# SC182029-V3R0-Servo.net
KiCad netlist of a schematic drawn in EAGLE
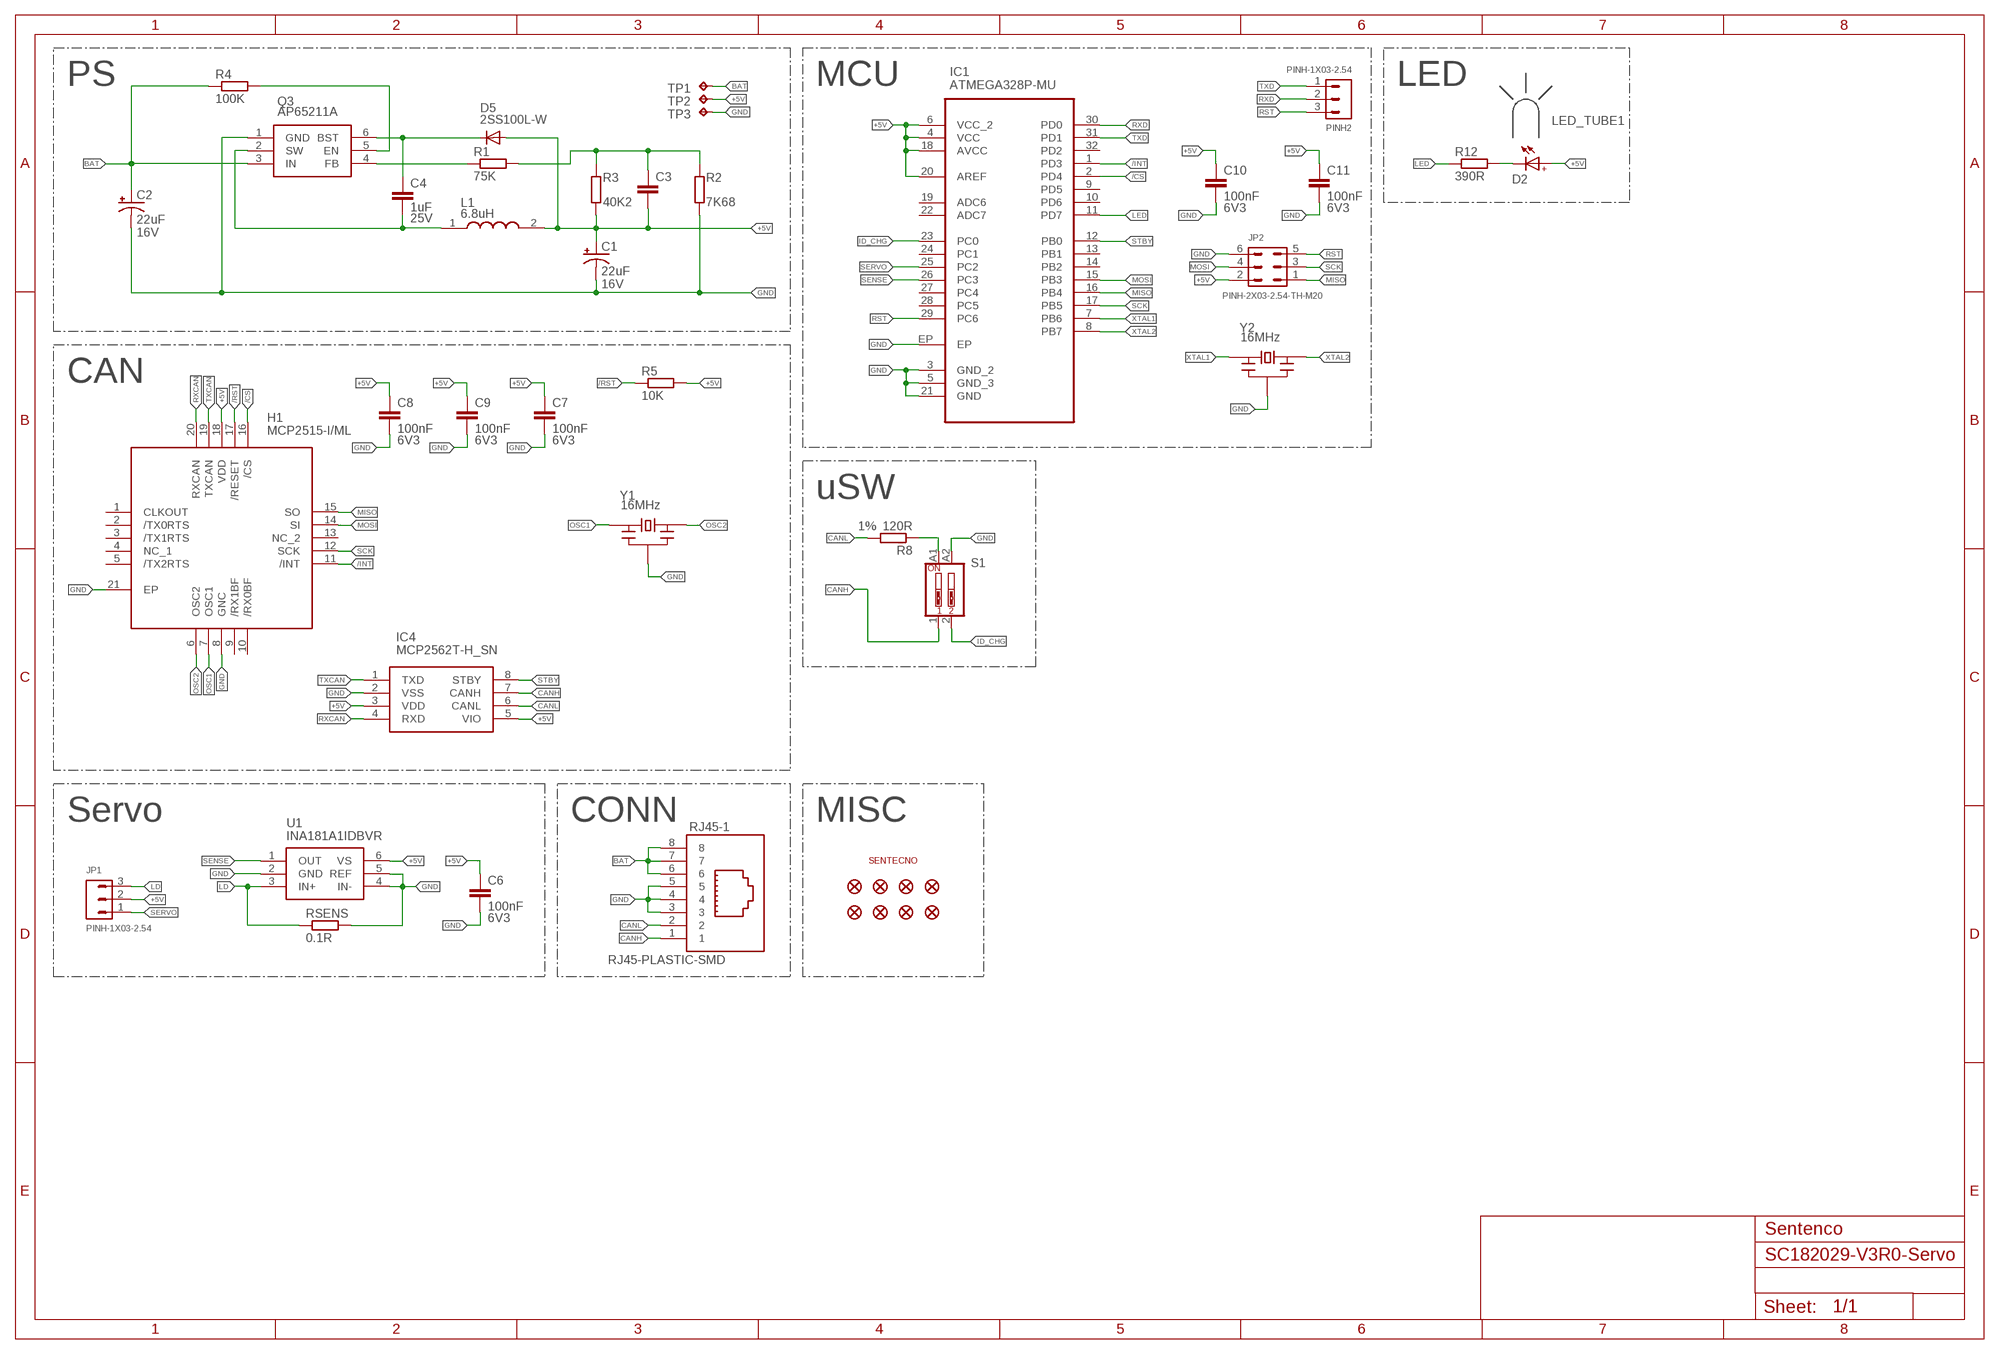
[diagram p0: schematic, sheet 1]

(export (version "E")
  (design (tool "Eeschema 10.0.6"))
  (components
    (comp (ref "C1")
      (value "22uF")
      (footprint "eagle-import:B")
      (fields
        (field (name "MAN1") "Illinois Capacitor / CDE")
        (field (name "MAN1PN") "226SML016MD4")
        (field (name "NOTES") "H5.5mm")
        (field (name "SENTPN") "CESMD-PB-226-16V")
        (field (name "VALUE2") "16V")
      )
      (libsource (lib "eagle-import") (part "COND_PANASONIC_EEE-B"))
    )
    (comp (ref "C2")
      (value "22uF")
      (footprint "eagle-import:B")
      (fields
        (field (name "MAN1") "Illinois Capacitor / CDE")
        (field (name "MAN1PN") "226SML016MD4")
        (field (name "NOTES") "H5.5mm")
        (field (name "SENTPN") "CESMD-PB-226-16V")
        (field (name "VALUE2") "16V")
      )
      (libsource (lib "eagle-import") (part "COND_PANASONIC_EEE-B"))
    )
    (comp (ref "C3")
      (value "COND_CERAMICO_SMD0603R")
      (footprint "eagle-import:C0603R")
      (fields (field (name "BLOCK") "NM"))
      (libsource (lib "eagle-import") (part "COND_CERAMICO_SMD0603R"))
    )
    (comp (ref "C4")
      (value "1uF")
      (footprint "eagle-import:C0603R")
      (fields
        (field (name "BLOCK") "0")
        (field (name "LAYER") "Top")
        (field (name "MAN1") "Taiyo Yuden")
        (field (name "MAN1PN") "TMK107B7105KA-T")
        (field (name "SENTPN") "CCSMD-0603-105-25V")
        (field (name "VALUE2") "25V")
      )
      (libsource (lib "eagle-import") (part "COND_CERAMICO_SMD0603R"))
    )
    (comp (ref "C6")
      (value "100nF")
      (footprint "eagle-import:C0603R")
      (fields
        (field (name "MAN1") "AVX")
        (field (name "MAN1PN") "0603YC104KAT2A")
        (field (name "SENTPN") "CCSMD-0603-104-6V3")
        (field (name "VALUE2") "6V3")
      )
      (libsource (lib "eagle-import") (part "COND_CERAMICO_SMD0603R"))
    )
    (comp (ref "C7")
      (value "100nF")
      (footprint "eagle-import:C0603R")
      (fields
        (field (name "MAN1") "AVX")
        (field (name "MAN1PN") "0603YC104KAT2A")
        (field (name "SENTPN") "CCSMD-0603-104-6V3")
        (field (name "VALUE2") "6V3")
      )
      (libsource (lib "eagle-import") (part "COND_CERAMICO_SMD0603R"))
    )
    (comp (ref "C8")
      (value "100nF")
      (footprint "eagle-import:C0603R")
      (fields
        (field (name "MAN1") "AVX")
        (field (name "MAN1PN") "0603YC104KAT2A")
        (field (name "SENTPN") "CCSMD-0603-104-6V3")
        (field (name "VALUE2") "6V3")
      )
      (libsource (lib "eagle-import") (part "COND_CERAMICO_SMD0603R"))
    )
    (comp (ref "C9")
      (value "100nF")
      (footprint "eagle-import:C0603R")
      (fields
        (field (name "MAN1") "AVX")
        (field (name "MAN1PN") "0603YC104KAT2A")
        (field (name "SENTPN") "CCSMD-0603-104-6V3")
        (field (name "VALUE2") "6V3")
      )
      (libsource (lib "eagle-import") (part "COND_CERAMICO_SMD0603R"))
    )
    (comp (ref "C10")
      (value "100nF")
      (footprint "eagle-import:C0603R")
      (fields
        (field (name "MAN1") "AVX")
        (field (name "MAN1PN") "0603YC104KAT2A")
        (field (name "SENTPN") "CCSMD-0603-104-6V3")
        (field (name "VALUE2") "6V3")
      )
      (libsource (lib "eagle-import") (part "COND_CERAMICO_SMD0603R"))
    )
    (comp (ref "C11")
      (value "100nF")
      (footprint "eagle-import:C0603R")
      (fields
        (field (name "MAN1") "AVX")
        (field (name "MAN1PN") "0603YC104KAT2A")
        (field (name "SENTPN") "CCSMD-0603-104-6V3")
        (field (name "VALUE2") "6V3")
      )
      (libsource (lib "eagle-import") (part "COND_CERAMICO_SMD0603R"))
    )
    (comp (ref "D2")
      (value "WL-SMCW-150060BS75000")
      (footprint "eagle-import:WL-SMCW_0603")
      (fields
        (field (name "MAN1") "Inolux")
        (field (name "MAN1PN") "IN-S63AT5G")
        (field (name "SENTPN") "LEDSMD-0603-GREEN")
      )
      (libsource (lib "eagle-import") (part "WL-SMCW-150060BS75000"))
    )
    (comp (ref "D5")
      (value "2SS100L-W")
      (footprint "eagle-import:SOD-123FL-CUSTOM")
      (fields
        (field (name "BLOCK") "NM")
        (field (name "LAYER") "Top")
        (field (name "MAN1") "Rectron")
        (field (name "MAN1PN") "2SS100L-W")
        (field (name "SENTPN") "2SS100L-W")
      )
      (libsource (lib "eagle-import") (part "DIODE"))
    )
    (comp (ref "FID1")
      (value "FIDUCIALUFIDUCIAL")
      (footprint "eagle-import:MICRO-FIDUCIAL")
      (libsource (lib "eagle-import") (part "FIDUCIALUFIDUCIAL"))
    )
    (comp (ref "FID2")
      (value "FIDUCIALUFIDUCIAL")
      (footprint "eagle-import:MICRO-FIDUCIAL")
      (libsource (lib "eagle-import") (part "FIDUCIALUFIDUCIAL"))
    )
    (comp (ref "FID3")
      (value "FIDUCIALUFIDUCIAL")
      (footprint "eagle-import:MICRO-FIDUCIAL")
      (libsource (lib "eagle-import") (part "FIDUCIALUFIDUCIAL"))
    )
    (comp (ref "FID4")
      (value "FIDUCIALUFIDUCIAL")
      (footprint "eagle-import:MICRO-FIDUCIAL")
      (libsource (lib "eagle-import") (part "FIDUCIALUFIDUCIAL"))
    )
    (comp (ref "FID5")
      (value "FIDUCIALUFIDUCIAL")
      (footprint "eagle-import:MICRO-FIDUCIAL")
      (libsource (lib "eagle-import") (part "FIDUCIALUFIDUCIAL"))
    )
    (comp (ref "FID6")
      (value "FIDUCIALUFIDUCIAL")
      (footprint "eagle-import:MICRO-FIDUCIAL")
      (libsource (lib "eagle-import") (part "FIDUCIALUFIDUCIAL"))
    )
    (comp (ref "FID7")
      (value "FIDUCIALUFIDUCIAL")
      (footprint "eagle-import:MICRO-FIDUCIAL")
      (libsource (lib "eagle-import") (part "FIDUCIALUFIDUCIAL"))
    )
    (comp (ref "FID8")
      (value "FIDUCIALUFIDUCIAL")
      (footprint "eagle-import:MICRO-FIDUCIAL")
      (libsource (lib "eagle-import") (part "FIDUCIALUFIDUCIAL"))
    )
    (comp (ref "H1")
      (value "MCP2515-I/ML")
      (footprint "eagle-import:QFN50P400X400X90-21N")
      (libsource (lib "eagle-import") (part "MCP2515-I/ML"))
    )
    (comp (ref "IC1")
      (value "ATMEGA328P-MU")
      (footprint "eagle-import:QFN50P500X500X100-33N")
      (libsource (lib "eagle-import") (part "ATMEGA328P-MU"))
    )
    (comp (ref "IC4")
      (value "MCP2562T-H_SN")
      (footprint "eagle-import:SOIC127P600X175-8N")
      (libsource (lib "eagle-import") (part "MCP2562T-H_SN"))
    )
    (comp (ref "JP1")
      (value "PINH-1X03-2.54")
      (footprint "eagle-import:PINH-1X03-2.54-1")
      (fields (field (name "MAN1") "Harwin") (field (name "MAN1PN") "M20-9990346"))
      (libsource (lib "eagle-import") (part "PINH-1X03-2.54"))
    )
    (comp (ref "JP2")
      (value "PINH-2X03-2.54-TH-M20")
      (footprint "eagle-import:HDRV6W64P254_2X3_762X508X868P")
      (libsource (lib "eagle-import") (part "PINH-2X03-2.54-TH-M20"))
    )
    (comp (ref "L1")
      (value "6.8uH")
      (footprint "eagle-import:NR5040")
      (libsource (lib "eagle-import") (part "NR5040"))
    )
    (comp (ref "LED_TUBE1")
      (value "LED_TUBEH1")
      (footprint "eagle-import:LED_TUBE_2")
      (libsource (lib "eagle-import") (part "LED_TUBEH1"))
    )
    (comp (ref "LOGO1")
      (value "LOGO_SENTECNOLOGO_6X4MM")
      (footprint "eagle-import:LOGO_6X4MM")
      (libsource (lib "eagle-import") (part "LOGO_SENTECNOLOGO_6X4MM"))
    )
    (comp (ref "PINH2")
      (value "PINH-1X03-2.54")
      (footprint "eagle-import:PINH-1X03-2.54-1")
      (fields (field (name "BLOCK") "NM"))
      (libsource (lib "eagle-import") (part "PINH-1X03-2.54"))
    )
    (comp (ref "Q3")
      (value "AP65211A")
      (footprint "eagle-import:SOT95P280X90-6N")
      (fields
        (field (name "BLOCK") "0")
        (field (name "LAYER") "Top")
        (field (name "MAN1PN") "AP65211A")
        (field (name "SENTPN") "AP65211A")
      )
      (libsource (lib "eagle-import") (part "AP65211A"))
    )
    (comp (ref "R1")
      (value "75K")
      (footprint "eagle-import:R0603R")
      (fields
        (field (name "BLOCK") "0")
        (field (name "LAYER") "Top")
        (field (name "MAN1") "Yageo")
        (field (name "MAN1PN") "RC0603JR-0775KL")
        (field (name "SENTPN") "RSMD-0603-75K")
      )
      (libsource (lib "eagle-import") (part "RES_CERAMICA_SMD0603R"))
    )
    (comp (ref "R2")
      (value "7K68")
      (footprint "eagle-import:R0603R")
      (fields
        (field (name "BLOCK") "0")
        (field (name "LAYER") "Top")
        (field (name "MAN1") "Bourns")
        (field (name "MAN1PN") "CR0603-FX-7681ELF")
        (field (name "MAN2") "RC0603FR-077K68L")
        (field (name "MAN2PN") "Yageo")
        (field (name "SENTPN") "RSMD-0603-7K68")
      )
      (libsource (lib "eagle-import") (part "RES_CERAMICA_SMD0603R"))
    )
    (comp (ref "R3")
      (value "40K2")
      (footprint "eagle-import:R0603R")
      (fields
        (field (name "BLOCK") "0")
        (field (name "LAYER") "Top")
        (field (name "MAN1") "Yageo")
        (field (name "MAN1PN") "RC0603FR-0740K2L")
        (field (name "SENTPN") "RSMD-0603-40K2")
      )
      (libsource (lib "eagle-import") (part "RES_CERAMICA_SMD0603R"))
    )
    (comp (ref "R4")
      (value "100K")
      (footprint "eagle-import:R0603R")
      (fields
        (field (name "BLOCK") "0")
        (field (name "LAYER") "Top")
        (field (name "MAN1") "Bourns")
        (field (name "MAN1PN") "CR0603-JW-104GLF")
        (field (name "SENTPN") "RSMD-0603-100K")
      )
      (libsource (lib "eagle-import") (part "RES_CERAMICA_SMD0603R"))
    )
    (comp (ref "R5")
      (value "10K")
      (footprint "eagle-import:R0603R")
      (fields
        (field (name "MAN1") "Bourns")
        (field (name "MAN1PN") "CR0603-JW-103ELF")
        (field (name "SENTPN") "RSMD-0603-10K")
      )
      (libsource (lib "eagle-import") (part "RES_CERAMICA_SMD0603R"))
    )
    (comp (ref "R8")
      (value "120R")
      (footprint "eagle-import:R0603R")
      (fields
        (field (name "MAN1") "Yageo")
        (field (name "MAN1PN") "RC0603FR-07120RL")
        (field (name "SENTPN") "RSMD-0603R-120R-10")
        (field (name "VALUE2") "1%")
      )
      (libsource (lib "eagle-import") (part "RES_CERAMICA_SMD0603R"))
    )
    (comp (ref "R12")
      (value "390R")
      (footprint "eagle-import:R0603R")
      (fields
        (field (name "MAN1") "Yageo")
        (field (name "MAN1PN") "RC0603FR-07390RL")
        (field (name "SENTPN") "RSMD-0603-390R")
      )
      (libsource (lib "eagle-import") (part "RES_CERAMICA_SMD0603R"))
    )
    (comp (ref "RJ45-1")
      (value "RJ45-PLASTIC-SMD")
      (footprint "eagle-import:73304111LF")
      (libsource (lib "eagle-import") (part "RJ45-PLASTIC-SMD"))
    )
    (comp (ref "RSENS")
      (value "0.1R")
      (footprint "eagle-import:R0603R")
      (fields
        (field (name "MAN1") "Yageo")
        (field (name "MAN1PN") "RL0603JR-070R1L")
        (field (name "SENTPN") "RSMD-0603-0R1")
      )
      (libsource (lib "eagle-import") (part "RES_CERAMICA_SMD0603R"))
    )
    (comp (ref "S1")
      (value "DIP-SW-2")
      (footprint "eagle-import:SMD-DIP-SWITCH-2P")
      (fields (field (name "SENTPN") "SWSMD-1x02"))
      (libsource (lib "eagle-import") (part "DIP-SW-2"))
    )
    (comp (ref "TP1")
      (value "TPTP08R")
      (footprint "eagle-import:TP0.8MMR")
      (libsource (lib "eagle-import") (part "TPTP08R"))
    )
    (comp (ref "TP2")
      (value "TPTP08R")
      (footprint "eagle-import:TP0.8MMR")
      (libsource (lib "eagle-import") (part "TPTP08R"))
    )
    (comp (ref "TP3")
      (value "TPTP08R")
      (footprint "eagle-import:TP0.8MMR")
      (libsource (lib "eagle-import") (part "TPTP08R"))
    )
    (comp (ref "U1")
      (value "INA181A1IDBVR")
      (footprint "eagle-import:SOT95P280X145-6N")
      (fields (field (name "SENTPN") "INA181A1IDBVR"))
      (libsource (lib "eagle-import") (part "INA181A1IDBVR"))
    )
    (comp (ref "Y1")
      (value "16MHz")
      (footprint "eagle-import:CSTNE16M0V530000R0")
      (fields (field (name "SENTPN") "CRES-3.2x1.3-16MHz"))
      (libsource (lib "eagle-import") (part "RESONADOR_CERAMICO-UNKN1"))
    )
    (comp (ref "Y2")
      (value "16MHz")
      (footprint "eagle-import:CSTNE16M0V530000R0")
      (fields (field (name "SENTPN") "CRES-3.2x1.3-16MHz"))
      (libsource (lib "eagle-import") (part "RESONADOR_CERAMICO-UNKN1"))
    )
  )
  (nets
    (net (code "1") (name "+5V") (class "Default")
      (node (ref "C1") (pin "PIN_1_POS") (pinfunction "+_PIN_1_POS") (pintype "passive"))
      (node (ref "C10") (pin "1") (pinfunction "1_1") (pintype "passive"))
      (node (ref "C11") (pin "1") (pinfunction "1_1") (pintype "passive"))
      (node (ref "C3") (pin "2") (pinfunction "2_2") (pintype "passive"))
      (node (ref "C6") (pin "1") (pinfunction "1_1") (pintype "passive"))
      (node (ref "C7") (pin "1") (pinfunction "1_1") (pintype "passive"))
      (node (ref "C8") (pin "1") (pinfunction "1_1") (pintype "passive"))
      (node (ref "C9") (pin "1") (pinfunction "1_1") (pintype "passive"))
      (node (ref "D2") (pin "2") (pinfunction "+_2") (pintype "passive"))
      (node (ref "D5") (pin "+") (pinfunction "A_+") (pintype "passive"))
      (node (ref "H1") (pin "18") (pinfunction "VDD_18") (pintype "power_in"))
      (node (ref "IC1") (pin "18") (pinfunction "AVCC_18") (pintype "power_in"))
      (node (ref "IC1") (pin "20") (pinfunction "AREF_20") (pintype "input"))
      (node (ref "IC1") (pin "4") (pinfunction "VCC_4") (pintype "power_in"))
      (node (ref "IC1") (pin "6") (pinfunction "VCC_2_6") (pintype "power_in"))
      (node (ref "IC4") (pin "3") (pinfunction "VDD_3") (pintype "power_in"))
      (node (ref "IC4") (pin "5") (pinfunction "VIO_5") (pintype "power_in"))
      (node (ref "JP1") (pin "2") (pinfunction "2_2") (pintype "bidirectional"))
      (node (ref "JP2") (pin "2") (pinfunction "2_2") (pintype "bidirectional"))
      (node (ref "L1") (pin "2") (pinfunction "2_2") (pintype "bidirectional"))
      (node (ref "R3") (pin "1") (pinfunction "1_1") (pintype "passive"))
      (node (ref "R5") (pin "2") (pinfunction "2_2") (pintype "passive"))
      (node (ref "TP2") (pin "TP") (pinfunction "TP_TP") (pintype "input"))
      (node (ref "U1") (pin "6") (pinfunction "VS_6") (pintype "power_in"))
    )
    (net (code "2") (name "BAT") (class "Default")
      (node (ref "C2") (pin "PIN_1_POS") (pinfunction "+_PIN_1_POS") (pintype "passive"))
      (node (ref "Q3") (pin "3") (pinfunction "IN_3") (pintype "bidirectional"))
      (node (ref "R4") (pin "1") (pinfunction "1_1") (pintype "passive"))
      (node (ref "RJ45-1") (pin "6") (pinfunction "6_6") (pintype "passive"))
      (node (ref "RJ45-1") (pin "7") (pinfunction "7_7") (pintype "passive"))
      (node (ref "RJ45-1") (pin "8") (pinfunction "8_8") (pintype "passive"))
      (node (ref "TP1") (pin "TP") (pinfunction "TP_TP") (pintype "input"))
    )
    (net (code "3") (name "CANH") (class "Default")
      (node (ref "IC4") (pin "7") (pinfunction "CANH_7") (pintype "bidirectional"))
      (node (ref "RJ45-1") (pin "1") (pinfunction "1_1") (pintype "passive"))
      (node (ref "S1") (pin "1") (pinfunction "1_1") (pintype "passive"))
    )
    (net (code "4") (name "CANL") (class "Default")
      (node (ref "IC4") (pin "6") (pinfunction "CANL_6") (pintype "bidirectional"))
      (node (ref "R8") (pin "2") (pinfunction "2_2") (pintype "passive"))
      (node (ref "RJ45-1") (pin "2") (pinfunction "2_2") (pintype "passive"))
    )
    (net (code "5") (name "GND") (class "Default")
      (node (ref "C1") (pin "PIN_2_NEG") (pinfunction "-_PIN_2_NEG") (pintype "passive"))
      (node (ref "C10") (pin "2") (pinfunction "2_2") (pintype "passive"))
      (node (ref "C11") (pin "2") (pinfunction "2_2") (pintype "passive"))
      (node (ref "C2") (pin "PIN_2_NEG") (pinfunction "-_PIN_2_NEG") (pintype "passive"))
      (node (ref "C6") (pin "2") (pinfunction "2_2") (pintype "passive"))
      (node (ref "C7") (pin "2") (pinfunction "2_2") (pintype "passive"))
      (node (ref "C8") (pin "2") (pinfunction "2_2") (pintype "passive"))
      (node (ref "C9") (pin "2") (pinfunction "2_2") (pintype "passive"))
      (node (ref "H1") (pin "21") (pinfunction "EP_21") (pintype "bidirectional"))
      (node (ref "H1") (pin "8") (pinfunction "GNC_8") (pintype "power_in"))
      (node (ref "IC1") (pin "21") (pinfunction "GND_21") (pintype "passive"))
      (node (ref "IC1") (pin "3") (pinfunction "GND_2_3") (pintype "passive"))
      (node (ref "IC1") (pin "5") (pinfunction "GND_3_5") (pintype "passive"))
      (node (ref "IC1") (pin "EP") (pinfunction "EP_EP") (pintype "passive"))
      (node (ref "IC4") (pin "2") (pinfunction "VSS_2") (pintype "power_in"))
      (node (ref "JP2") (pin "6") (pinfunction "6_6") (pintype "bidirectional"))
      (node (ref "Q3") (pin "1") (pinfunction "GND_1") (pintype "bidirectional"))
      (node (ref "R2") (pin "1") (pinfunction "1_1") (pintype "passive"))
      (node (ref "RJ45-1") (pin "3") (pinfunction "3_3") (pintype "passive"))
      (node (ref "RJ45-1") (pin "4") (pinfunction "4_4") (pintype "passive"))
      (node (ref "RJ45-1") (pin "5") (pinfunction "5_5") (pintype "passive"))
      (node (ref "RSENS") (pin "2") (pinfunction "2_2") (pintype "passive"))
      (node (ref "S1") (pin "A2") (pinfunction "A2_A2") (pintype "passive"))
      (node (ref "TP3") (pin "TP") (pinfunction "TP_TP") (pintype "input"))
      (node (ref "U1") (pin "2") (pinfunction "GND_2") (pintype "power_in"))
      (node (ref "U1") (pin "4") (pinfunction "IN-_4") (pintype "input"))
      (node (ref "U1") (pin "5") (pinfunction "REF_5") (pintype "input"))
      (node (ref "Y1") (pin "2") (pinfunction "GND_2") (pintype "bidirectional"))
      (node (ref "Y2") (pin "2") (pinfunction "GND_2") (pintype "bidirectional"))
    )
    (net (code "6") (name "ID_CHG") (class "Default")
      (node (ref "IC1") (pin "23") (pinfunction "PC0_23") (pintype "bidirectional"))
      (node (ref "S1") (pin "2") (pinfunction "2_2") (pintype "passive"))
    )
    (net (code "7") (name "LD") (class "Default")
      (node (ref "JP1") (pin "3") (pinfunction "3_3") (pintype "bidirectional"))
      (node (ref "RSENS") (pin "1") (pinfunction "1_1") (pintype "passive"))
      (node (ref "U1") (pin "3") (pinfunction "IN+_3") (pintype "input"))
    )
    (net (code "8") (name "LED") (class "Default")
      (node (ref "IC1") (pin "11") (pinfunction "PD7_11") (pintype "bidirectional"))
      (node (ref "R12") (pin "1") (pinfunction "1_1") (pintype "passive"))
    )
    (net (code "9") (name "MISO") (class "Default")
      (node (ref "H1") (pin "15") (pinfunction "SO_15") (pintype "output"))
      (node (ref "IC1") (pin "16") (pinfunction "PB4_16") (pintype "bidirectional"))
      (node (ref "JP2") (pin "1") (pinfunction "1_1") (pintype "bidirectional"))
    )
    (net (code "10") (name "MOSI") (class "Default")
      (node (ref "H1") (pin "14") (pinfunction "SI_14") (pintype "input"))
      (node (ref "IC1") (pin "15") (pinfunction "PB3_15") (pintype "bidirectional"))
      (node (ref "JP2") (pin "4") (pinfunction "4_4") (pintype "bidirectional"))
    )
    (net (code "11") (name "Net-(C3-Pad1)") (class "Default")
      (node (ref "C3") (pin "1") (pinfunction "1_1") (pintype "passive"))
      (node (ref "R1") (pin "2") (pinfunction "2_2") (pintype "passive"))
      (node (ref "R2") (pin "2") (pinfunction "2_2") (pintype "passive"))
      (node (ref "R3") (pin "2") (pinfunction "2_2") (pintype "passive"))
    )
    (net (code "12") (name "Net-(D2--)") (class "Default")
      (node (ref "D2") (pin "1") (pinfunction "-_1") (pintype "passive"))
      (node (ref "R12") (pin "2") (pinfunction "2_2") (pintype "passive"))
    )
    (net (code "13") (name "Net-(Q3-BST)") (class "Default")
      (node (ref "C4") (pin "1") (pinfunction "1_1") (pintype "passive"))
      (node (ref "D5") (pin "-") (pinfunction "K_-") (pintype "passive"))
      (node (ref "D5") (pin "--") (pinfunction "K_--") (pintype "passive"))
      (node (ref "Q3") (pin "6") (pinfunction "BST_6") (pintype "bidirectional"))
    )
    (net (code "14") (name "Net-(Q3-EN)") (class "Default")
      (node (ref "Q3") (pin "5") (pinfunction "EN_5") (pintype "bidirectional"))
      (node (ref "R4") (pin "2") (pinfunction "2_2") (pintype "passive"))
    )
    (net (code "15") (name "Net-(Q3-FB)") (class "Default")
      (node (ref "Q3") (pin "4") (pinfunction "FB_4") (pintype "bidirectional"))
      (node (ref "R1") (pin "1") (pinfunction "1_1") (pintype "passive"))
    )
    (net (code "16") (name "Net-(Q3-SW)") (class "Default")
      (node (ref "C4") (pin "2") (pinfunction "2_2") (pintype "passive"))
      (node (ref "L1") (pin "1") (pinfunction "1_1") (pintype "bidirectional"))
      (node (ref "Q3") (pin "2") (pinfunction "SW_2") (pintype "bidirectional"))
    )
    (net (code "17") (name "Net-(R8-Pad1)") (class "Default")
      (node (ref "R8") (pin "1") (pinfunction "1_1") (pintype "passive"))
      (node (ref "S1") (pin "A1") (pinfunction "A1_A1") (pintype "passive"))
    )
    (net (code "18") (name "OSC1") (class "Default")
      (node (ref "H1") (pin "7") (pinfunction "OSC1_7") (pintype "input"))
      (node (ref "Y1") (pin "3") (pinfunction "OUT_3") (pintype "bidirectional"))
    )
    (net (code "19") (name "OSC2") (class "Default")
      (node (ref "H1") (pin "6") (pinfunction "OSC2_6") (pintype "output"))
      (node (ref "Y1") (pin "1") (pinfunction "IN_1") (pintype "bidirectional"))
    )
    (net (code "20") (name "RST") (class "Default")
      (node (ref "IC1") (pin "29") (pinfunction "PC6_29") (pintype "bidirectional"))
      (node (ref "JP2") (pin "5") (pinfunction "5_5") (pintype "bidirectional"))
      (node (ref "PINH2") (pin "3") (pinfunction "3_3") (pintype "bidirectional"))
    )
    (net (code "21") (name "RXCAN") (class "Default")
      (node (ref "H1") (pin "20") (pinfunction "RXCAN_20") (pintype "input"))
      (node (ref "IC4") (pin "4") (pinfunction "RXD_4") (pintype "output"))
    )
    (net (code "22") (name "RXD") (class "Default")
      (node (ref "IC1") (pin "30") (pinfunction "PD0_30") (pintype "bidirectional"))
      (node (ref "PINH2") (pin "2") (pinfunction "2_2") (pintype "bidirectional"))
    )
    (net (code "23") (name "SCK") (class "Default")
      (node (ref "H1") (pin "12") (pinfunction "SCK_12") (pintype "input"))
      (node (ref "IC1") (pin "17") (pinfunction "PB5_17") (pintype "bidirectional"))
      (node (ref "JP2") (pin "3") (pinfunction "3_3") (pintype "bidirectional"))
    )
    (net (code "24") (name "SENSE") (class "Default")
      (node (ref "IC1") (pin "26") (pinfunction "PC3_26") (pintype "bidirectional"))
      (node (ref "U1") (pin "1") (pinfunction "OUT_1") (pintype "output"))
    )
    (net (code "25") (name "SERVO") (class "Default")
      (node (ref "IC1") (pin "25") (pinfunction "PC2_25") (pintype "bidirectional"))
      (node (ref "JP1") (pin "1") (pinfunction "1_1") (pintype "bidirectional"))
    )
    (net (code "26") (name "STBY") (class "Default")
      (node (ref "IC1") (pin "12") (pinfunction "PB0_12") (pintype "bidirectional"))
      (node (ref "IC4") (pin "8") (pinfunction "STBY_8") (pintype "input"))
    )
    (net (code "27") (name "TXCAN") (class "Default")
      (node (ref "H1") (pin "19") (pinfunction "TXCAN_19") (pintype "output"))
      (node (ref "IC4") (pin "1") (pinfunction "TXD_1") (pintype "input"))
    )
    (net (code "28") (name "TXD") (class "Default")
      (node (ref "IC1") (pin "31") (pinfunction "PD1_31") (pintype "bidirectional"))
      (node (ref "PINH2") (pin "1") (pinfunction "1_1") (pintype "bidirectional"))
    )
    (net (code "29") (name "XTAL1") (class "Default")
      (node (ref "IC1") (pin "7") (pinfunction "PB6_7") (pintype "bidirectional"))
      (node (ref "Y2") (pin "3") (pinfunction "OUT_3") (pintype "bidirectional"))
    )
    (net (code "30") (name "XTAL2") (class "Default")
      (node (ref "IC1") (pin "8") (pinfunction "PB7_8") (pintype "bidirectional"))
      (node (ref "Y2") (pin "1") (pinfunction "IN_1") (pintype "bidirectional"))
    )
    (net (code "31") (name "unconnected-(H1-CLKOUT-Pad1)") (class "Default")
      (node (ref "H1") (pin "1") (pinfunction "CLKOUT_1") (pintype "output"))
    )
    (net (code "32") (name "unconnected-(H1-NC_1-Pad4)") (class "Default")
      (node (ref "H1") (pin "4") (pinfunction "NC_1_4") (pintype "bidirectional"))
    )
    (net (code "33") (name "unconnected-(H1-NC_2-Pad13)") (class "Default")
      (node (ref "H1") (pin "13") (pinfunction "NC_2_13") (pintype "bidirectional"))
    )
    (net (code "34") (name "unconnected-(H1-{slash}RX0BF-Pad10)") (class "Default")
      (node (ref "H1") (pin "10") (pinfunction "/RX0BF_10") (pintype "output"))
    )
    (net (code "35") (name "unconnected-(H1-{slash}RX1BF-Pad9)") (class "Default")
      (node (ref "H1") (pin "9") (pinfunction "/RX1BF_9") (pintype "output"))
    )
    (net (code "36") (name "unconnected-(H1-{slash}TX0RTS-Pad2)") (class "Default")
      (node (ref "H1") (pin "2") (pinfunction "/TX0RTS_2") (pintype "input"))
    )
    (net (code "37") (name "unconnected-(H1-{slash}TX1RTS-Pad3)") (class "Default")
      (node (ref "H1") (pin "3") (pinfunction "/TX1RTS_3") (pintype "input"))
    )
    (net (code "38") (name "unconnected-(H1-{slash}TX2RTS-Pad5)") (class "Default")
      (node (ref "H1") (pin "5") (pinfunction "/TX2RTS_5") (pintype "input"))
    )
    (net (code "39") (name "unconnected-(IC1-ADC6-Pad19)") (class "Default")
      (node (ref "IC1") (pin "19") (pinfunction "ADC6_19") (pintype "input"))
    )
    (net (code "40") (name "unconnected-(IC1-ADC7-Pad22)") (class "Default")
      (node (ref "IC1") (pin "22") (pinfunction "ADC7_22") (pintype "input"))
    )
    (net (code "41") (name "unconnected-(IC1-PB1-Pad13)") (class "Default")
      (node (ref "IC1") (pin "13") (pinfunction "PB1_13") (pintype "bidirectional"))
    )
    (net (code "42") (name "unconnected-(IC1-PB2-Pad14)") (class "Default")
      (node (ref "IC1") (pin "14") (pinfunction "PB2_14") (pintype "bidirectional"))
    )
    (net (code "43") (name "unconnected-(IC1-PC1-Pad24)") (class "Default")
      (node (ref "IC1") (pin "24") (pinfunction "PC1_24") (pintype "bidirectional"))
    )
    (net (code "44") (name "unconnected-(IC1-PC4-Pad27)") (class "Default")
      (node (ref "IC1") (pin "27") (pinfunction "PC4_27") (pintype "bidirectional"))
    )
    (net (code "45") (name "unconnected-(IC1-PC5-Pad28)") (class "Default")
      (node (ref "IC1") (pin "28") (pinfunction "PC5_28") (pintype "bidirectional"))
    )
    (net (code "46") (name "unconnected-(IC1-PD2-Pad32)") (class "Default")
      (node (ref "IC1") (pin "32") (pinfunction "PD2_32") (pintype "bidirectional"))
    )
    (net (code "47") (name "unconnected-(IC1-PD5-Pad9)") (class "Default")
      (node (ref "IC1") (pin "9") (pinfunction "PD5_9") (pintype "bidirectional"))
    )
    (net (code "48") (name "unconnected-(IC1-PD6-Pad10)") (class "Default")
      (node (ref "IC1") (pin "10") (pinfunction "PD6_10") (pintype "bidirectional"))
    )
    (net (code "49") (name "{slash}CS") (class "Default")
      (node (ref "H1") (pin "16") (pinfunction "/CS_16") (pintype "input"))
      (node (ref "IC1") (pin "2") (pinfunction "PD4_2") (pintype "bidirectional"))
    )
    (net (code "50") (name "{slash}INT") (class "Default")
      (node (ref "H1") (pin "11") (pinfunction "/INT_11") (pintype "output"))
      (node (ref "IC1") (pin "1") (pinfunction "PD3_1") (pintype "bidirectional"))
    )
    (net (code "51") (name "{slash}RST") (class "Default")
      (node (ref "H1") (pin "17") (pinfunction "/RESET_17") (pintype "input"))
      (node (ref "R5") (pin "1") (pinfunction "1_1") (pintype "passive"))
    )
  )
)
